# CAN.net
KiCad netlist of a schematic drawn in Altium Designer
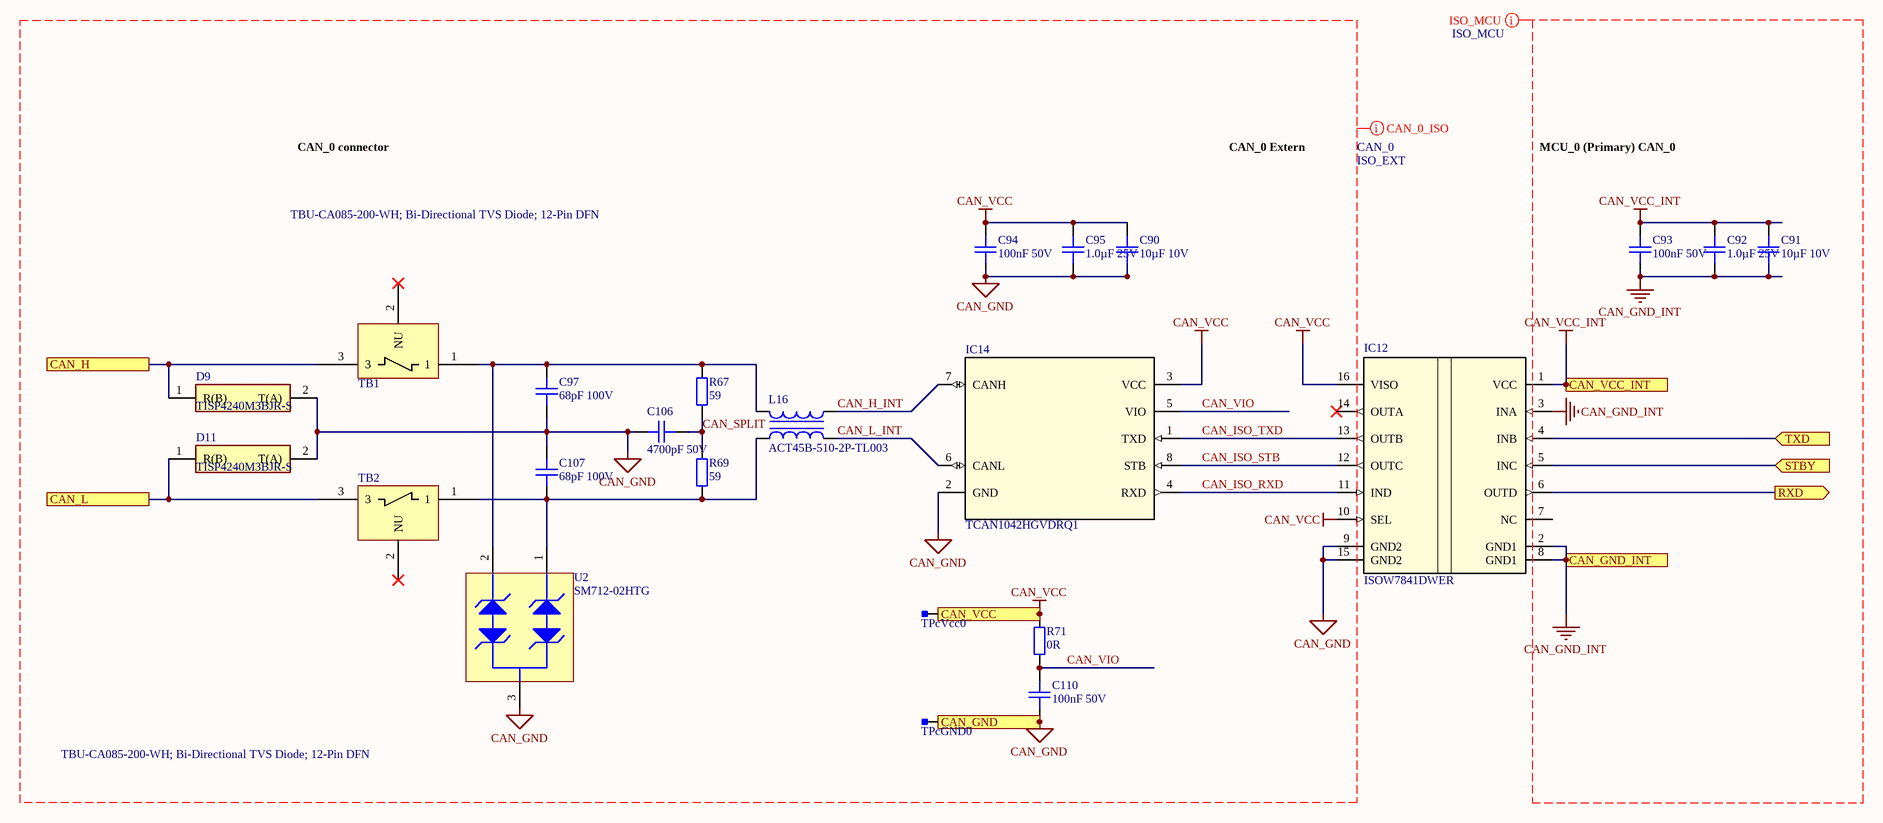
[diagram p0: CAN.SchDoc]

(export (version "E")
  (design (tool "Eeschema 10.0.6"))
  (components
    (comp (ref "C90")
      (value "10µF 10V")
      (footprint "0805C")
      (description "Ceramic, 10µF, ±10%, 10V, X7R, –55 to 125°C, 0805 (2012),RoHS, Automotive")
      (fields (field (name "PART NUMBER") "GCJ21BR71A106KE01") (field (name "TOLERANCE") "±10%"))
      (libsource (lib "master-010106") (part "gen_C_ceramic_10u_10V_X7R_0805"))
    )
    (comp (ref "C91")
      (value "10µF 10V")
      (footprint "0805C")
      (description "Ceramic, 10µF, ±10%, 10V, X7R, –55 to 125°C, 0805 (2012),RoHS, Automotive")
      (fields (field (name "PART NUMBER") "GCJ21BR71A106KE01") (field (name "TOLERANCE") "±10%"))
      (libsource (lib "master-010106") (part "gen_C_ceramic_10u_10V_X7R_0805"))
    )
    (comp (ref "C92")
      (value "1.0µF 25V")
      (footprint "0603C")
      (description "Ceramic, 1.0µF, ±10%, 25V, X7R, –55 to 125°C, 0603 (1608),RoHS, Automotive")
      (fields (field (name "PART NUMBER") "GCJ188R71E105KA01") (field (name "TOLERANCE") "±10%"))
      (libsource (lib "master-010106") (part "gen_C_ceramic_1u_25V_X7R_0603"))
    )
    (comp (ref "C93")
      (value "100nF 50V")
      (footprint "0603C")
      (description "Ceramic, 100nF, ±10%, 50V, X7R, –55 to 125°C, 0603 (1608),RoHS, Automotive")
      (fields (field (name "PART NUMBER") "GCJ188R71H104KA12") (field (name "TOLERANCE") "±10%"))
      (libsource (lib "master-010106") (part "C"))
    )
    (comp (ref "C94")
      (value "100nF 50V")
      (footprint "0603C")
      (description "Ceramic, 100nF, ±10%, 50V, X7R, –55 to 125°C, 0603 (1608),RoHS, Automotive")
      (fields (field (name "PART NUMBER") "GCJ188R71H104KA12") (field (name "TOLERANCE") "±10%"))
      (libsource (lib "master-010106") (part "C"))
    )
    (comp (ref "C95")
      (value "1.0µF 25V")
      (footprint "0603C")
      (description "Ceramic, 1.0µF, ±10%, 25V, X7R, –55 to 125°C, 0603 (1608),RoHS, Automotive")
      (fields (field (name "PART NUMBER") "GCJ188R71E105KA01") (field (name "TOLERANCE") "±10%"))
      (libsource (lib "master-010106") (part "gen_C_ceramic_1u_25V_X7R_0603"))
    )
    (comp (ref "C97")
      (value "68pF 100V")
      (footprint "0603C")
      (description "Ceramic, 68pF, ±5%, 100V, X7R, 25 to 125°C, 0603 (1608),RoHS, Automotive")
      (fields (field (name "PART NUMBER") "GCM1885C2A680JA16") (field (name "TOLERANCE") "±5%"))
      (libsource (lib "master-010106") (part "gen_C_ceramic_68p_100V_X7R_0603"))
    )
    (comp (ref "C106")
      (value "4700pF 50V")
      (footprint "0603C")
      (description "Ceramic, 4700pF, 0603, ±5%, 50V, C0G")
      (fields (field (name "PART NUMBER") "GRT1885C1H472JA02"))
      (libsource (lib "master-010106") (part "C"))
    )
    (comp (ref "C107")
      (value "68pF 100V")
      (footprint "0603C")
      (description "Ceramic, 68pF, ±5%, 100V, X7R, 25 to 125°C, 0603 (1608),RoHS, Automotive")
      (fields (field (name "PART NUMBER") "GCM1885C2A680JA16") (field (name "TOLERANCE") "±5%"))
      (libsource (lib "master-010106") (part "gen_C_ceramic_68p_100V_X7R_0603"))
    )
    (comp (ref "C110")
      (value "100nF 50V")
      (footprint "0603C")
      (description "Ceramic, 100nF, ±10%, 50V, X7R, –55 to 125°C, 0603 (1608),RoHS, Automotive")
      (fields (field (name "PART NUMBER") "GCJ188R71H104KA12") (field (name "TOLERANCE") "±10%"))
      (libsource (lib "master-010106") (part "C"))
    )
    (comp (ref "D9")
      (value "TISP4240M3BJR-S")
      (footprint "SamacSys:SMBJ(DO-214AA)")
      (description "Thyristor")
      (fields (field (name "MOUSER PART NUMBER") "652-TISP4240M3BJR-S"))
      (libsource (lib "*") (part "TISP4240M3BJR-S"))
    )
    (comp (ref "D11")
      (value "TISP4240M3BJR-S")
      (footprint "SamacSys:SMBJ(DO-214AA)")
      (description "Thyristor")
      (fields (field (name "MOUSER PART NUMBER") "652-TISP4240M3BJR-S"))
      (libsource (lib "*") (part "TISP4240M3BJR-S"))
    )
    (comp (ref "IC12")
      (value "ISOW7841DWER")
      (footprint "DWE0016A")
      (description "Imported")
      (fields (field (name "MANUFACTURER") "Texas Instruments"))
      (libsource (lib "ti-import") (part "ISOW7841DWER"))
    )
    (comp (ref "IC14")
      (value "TCAN1042HGVDRQ1")
      (footprint "D0008A_N")
      (description "Imported")
      (fields (field (name "PARTNUMBER") "TCAN1042HGVDQ1") (field (name "MANUFACTURER") "Texas Instruments"))
      (libsource (lib "ti-import") (part "TCAN1042HGVDRQ1"))
    )
    (comp (ref "L16")
      (value "ACT45B-510-2P-TL003")
      (footprint "TDK-ACT45B-510-2P-TL003-4_V")
      (fields (field (name "MANUFACTURER") "TDK"))
      (libsource (lib "Altium Content Vault") (part "TDK-ACXXXXX-XXX-2P-T000-4"))
    )
    (comp (ref "R67")
      (value "59")
      (footprint "0805R")
      (description "SMD Resistor 59R 0805")
      (fields (field (name "PART NUMBER") "gen_R_62R_0603") (field (name "TOLERANCE") "1%"))
      (libsource (lib "master-010106") (part "gen_R_59R_0805"))
    )
    (comp (ref "R69")
      (value "59")
      (footprint "0805R")
      (description "SMD Resistor 59R 0805")
      (fields (field (name "PART NUMBER") "gen_R_62R_0603") (field (name "TOLERANCE") "1%"))
      (libsource (lib "master-010106") (part "gen_R_59R_0805"))
    )
    (comp (ref "R71")
      (value "0R")
      (footprint "0603R")
      (description "SMD Resistor 0R 0603")
      (fields (field (name "PART NUMBER") "gen_R_0R_0603") (field (name "POWER") "0.1W"))
      (libsource (lib "master-010106") (part "gen_R_0R_0603"))
    )
    (comp (ref "TB1")
      (value "TBU-CA085-200-WH; Bi-Directional TVS Diode; 12-Pin DFN")
      (footprint "Bourns-TBU-CA")
      (libsource (lib "master-010106") (part "TBU-CA085-200-WH"))
    )
    (comp (ref "TB2")
      (value "TBU-CA085-200-WH; Bi-Directional TVS Diode; 12-Pin DFN")
      (footprint "Bourns-TBU-CA")
      (libsource (lib "") (part "TBU-CA085-200-WH_1"))
    )
    (comp (ref "TPcGND0")
      (value "Testpoint_Square")
      (footprint "Testpoint_S1")
      (description "Testpoint, square")
      (libsource (lib "OE750") (part "Testpoint_Square"))
    )
    (comp (ref "TPcVcc0")
      (value "Testpoint_Square")
      (footprint "Testpoint_S1")
      (description "Testpoint, square")
      (libsource (lib "OE750") (part "Testpoint_Square"))
    )
    (comp (ref "U2")
      (value "SM712-02HTG")
      (footprint "LFUS-SOT23-3_V")
      (description "TVS Diode Array, 600 W, 12 V, -40 to 125 degC, 3-Pin SOT23, RoHS, Tape and Reel")
      (fields (field (name "MANUFACTURER") "Littelfuse"))
      (libsource (lib "Altium Content Vault") (part "LFUS-SM712-SOT23-3"))
    )
  )
  (nets
    (net (code "1") (name "/CAN_H") (class "Default")
      (node (ref "D9") (pin "1") (pinfunction "R(B)_1") (pintype "passive"))
      (node (ref "TB1") (pin "3") (pinfunction "3_3") (pintype "passive"))
    )
    (net (code "2") (name "/CAN_H_INT") (class "Default")
      (node (ref "IC14") (pin "7") (pinfunction "CANH_7") (pintype "bidirectional"))
      (node (ref "L16") (pin "3") (pinfunction "3_3") (pintype "passive"))
    )
    (net (code "3") (name "/CAN_ISO_RXD") (class "Default")
      (node (ref "IC12") (pin "11") (pinfunction "IND_11") (pintype "input"))
      (node (ref "IC14") (pin "4") (pinfunction "RXD_4") (pintype "output"))
    )
    (net (code "4") (name "/CAN_ISO_STB") (class "Default")
      (node (ref "IC12") (pin "12") (pinfunction "OUTC_12") (pintype "output"))
      (node (ref "IC14") (pin "8") (pinfunction "STB_8") (pintype "input"))
    )
    (net (code "5") (name "/CAN_ISO_TXD") (class "Default")
      (node (ref "IC12") (pin "13") (pinfunction "OUTB_13") (pintype "output"))
      (node (ref "IC14") (pin "1") (pinfunction "TXD_1") (pintype "input"))
    )
    (net (code "6") (name "/CAN_L") (class "Default")
      (node (ref "D11") (pin "1") (pinfunction "R(B)_1") (pintype "passive"))
      (node (ref "TB2") (pin "3") (pinfunction "3_3") (pintype "passive"))
    )
    (net (code "7") (name "/CAN_L_INT") (class "Default")
      (node (ref "IC14") (pin "6") (pinfunction "CANL_6") (pintype "bidirectional"))
      (node (ref "L16") (pin "4") (pinfunction "4_4") (pintype "passive"))
    )
    (net (code "8") (name "/CAN_SPLIT") (class "Default")
      (node (ref "C106") (pin "2") (pinfunction "2_2") (pintype "passive"))
      (node (ref "R67") (pin "1") (pinfunction "1_1") (pintype "passive"))
      (node (ref "R69") (pin "2") (pinfunction "2_2") (pintype "passive"))
    )
    (net (code "9") (name "/CAN_VIO") (class "Default")
      (node (ref "C110") (pin "2") (pinfunction "2_2") (pintype "passive"))
      (node (ref "IC14") (pin "5") (pinfunction "VIO_5") (pintype "power_in"))
      (node (ref "R71") (pin "2") (pinfunction "2_2") (pintype "passive"))
    )
    (net (code "10") (name "/RXD") (class "Default")
      (node (ref "IC12") (pin "6") (pinfunction "OUTD_6") (pintype "output"))
    )
    (net (code "11") (name "/STBY") (class "Default")
      (node (ref "IC12") (pin "5") (pinfunction "INC_5") (pintype "input"))
    )
    (net (code "12") (name "/TXD") (class "Default")
      (node (ref "IC12") (pin "4") (pinfunction "INB_4") (pintype "input"))
    )
    (net (code "13") (name "CAN_GND") (class "Default")
      (node (ref "C106") (pin "1") (pinfunction "1_1") (pintype "passive"))
      (node (ref "C107") (pin "2") (pinfunction "2_2") (pintype "passive"))
      (node (ref "C110") (pin "1") (pinfunction "1_1") (pintype "passive"))
      (node (ref "C90") (pin "2") (pinfunction "2_2") (pintype "passive"))
      (node (ref "C94") (pin "1") (pinfunction "1_1") (pintype "passive"))
      (node (ref "C95") (pin "1") (pinfunction "1_1") (pintype "passive"))
      (node (ref "C97") (pin "1") (pinfunction "1_1") (pintype "passive"))
      (node (ref "D11") (pin "2") (pinfunction "T(A)_2") (pintype "passive"))
      (node (ref "D9") (pin "2") (pinfunction "T(A)_2") (pintype "passive"))
      (node (ref "IC12") (pin "15") (pinfunction "GND2_15") (pintype "power_in"))
      (node (ref "IC12") (pin "9") (pinfunction "GND2_9") (pintype "power_in"))
      (node (ref "IC14") (pin "2") (pinfunction "GND_2") (pintype "power_in"))
      (node (ref "TPcGND0") (pin "1") (pinfunction "1_1") (pintype "passive"))
      (node (ref "U2") (pin "3") (pinfunction "3_3") (pintype "passive"))
    )
    (net (code "14") (name "CAN_GND_INT") (class "Default")
      (node (ref "C91") (pin "2") (pinfunction "2_2") (pintype "passive"))
      (node (ref "C92") (pin "1") (pinfunction "1_1") (pintype "passive"))
      (node (ref "C93") (pin "1") (pinfunction "1_1") (pintype "passive"))
      (node (ref "IC12") (pin "2") (pinfunction "GND1_2") (pintype "power_in"))
      (node (ref "IC12") (pin "3") (pinfunction "INA_3") (pintype "input"))
      (node (ref "IC12") (pin "8") (pinfunction "GND1_8") (pintype "power_in"))
    )
    (net (code "15") (name "CAN_VCC") (class "Default")
      (node (ref "C90") (pin "1") (pinfunction "1_1") (pintype "passive"))
      (node (ref "C94") (pin "2") (pinfunction "2_2") (pintype "passive"))
      (node (ref "C95") (pin "2") (pinfunction "2_2") (pintype "passive"))
      (node (ref "IC12") (pin "10") (pinfunction "SEL_10") (pintype "input"))
      (node (ref "IC12") (pin "16") (pinfunction "VISO_16") (pintype "power_in"))
      (node (ref "IC14") (pin "3") (pinfunction "VCC_3") (pintype "power_in"))
      (node (ref "R71") (pin "1") (pinfunction "1_1") (pintype "passive"))
      (node (ref "TPcVcc0") (pin "1") (pinfunction "1_1") (pintype "passive"))
    )
    (net (code "16") (name "CAN_VCC_INT") (class "Default")
      (node (ref "C91") (pin "1") (pinfunction "1_1") (pintype "passive"))
      (node (ref "C92") (pin "2") (pinfunction "2_2") (pintype "passive"))
      (node (ref "C93") (pin "2") (pinfunction "2_2") (pintype "passive"))
      (node (ref "IC12") (pin "1") (pinfunction "VCC_1") (pintype "power_in"))
    )
    (net (code "17") (name "Net-(C97-Pad2)") (class "Default")
      (node (ref "C97") (pin "2") (pinfunction "2_2") (pintype "passive"))
      (node (ref "L16") (pin "2") (pinfunction "2_2") (pintype "passive"))
      (node (ref "R67") (pin "2") (pinfunction "2_2") (pintype "passive"))
      (node (ref "TB1") (pin "1") (pinfunction "1_1") (pintype "passive"))
      (node (ref "U2") (pin "2") (pinfunction "2_2") (pintype "passive"))
    )
    (net (code "18") (name "Net-(C107-Pad1)") (class "Default")
      (node (ref "C107") (pin "1") (pinfunction "1_1") (pintype "passive"))
      (node (ref "L16") (pin "1") (pinfunction "1_1") (pintype "passive"))
      (node (ref "R69") (pin "1") (pinfunction "1_1") (pintype "passive"))
      (node (ref "TB2") (pin "1") (pinfunction "1_1") (pintype "passive"))
      (node (ref "U2") (pin "1") (pinfunction "1_1") (pintype "passive"))
    )
    (net (code "19") (name "unconnected-(IC12-NC-Pad7)") (class "Default")
      (node (ref "IC12") (pin "7") (pinfunction "NC_7") (pintype "passive"))
    )
    (net (code "20") (name "unconnected-(IC12-OUTA-Pad14)") (class "Default")
      (node (ref "IC12") (pin "14") (pinfunction "OUTA_14") (pintype "output+no_connect"))
    )
    (net (code "21") (name "unconnected-(TB1-NU-Pad2)") (class "Default")
      (node (ref "TB1") (pin "2") (pinfunction "NU_2") (pintype "passive+no_connect"))
    )
    (net (code "22") (name "unconnected-(TB2-NU-Pad2)") (class "Default")
      (node (ref "TB2") (pin "2") (pinfunction "NU_2") (pintype "passive+no_connect"))
    )
  )
)
